# KIT_STM32F103C8T6.net
KiCad netlist of a schematic drawn in Altium Designer
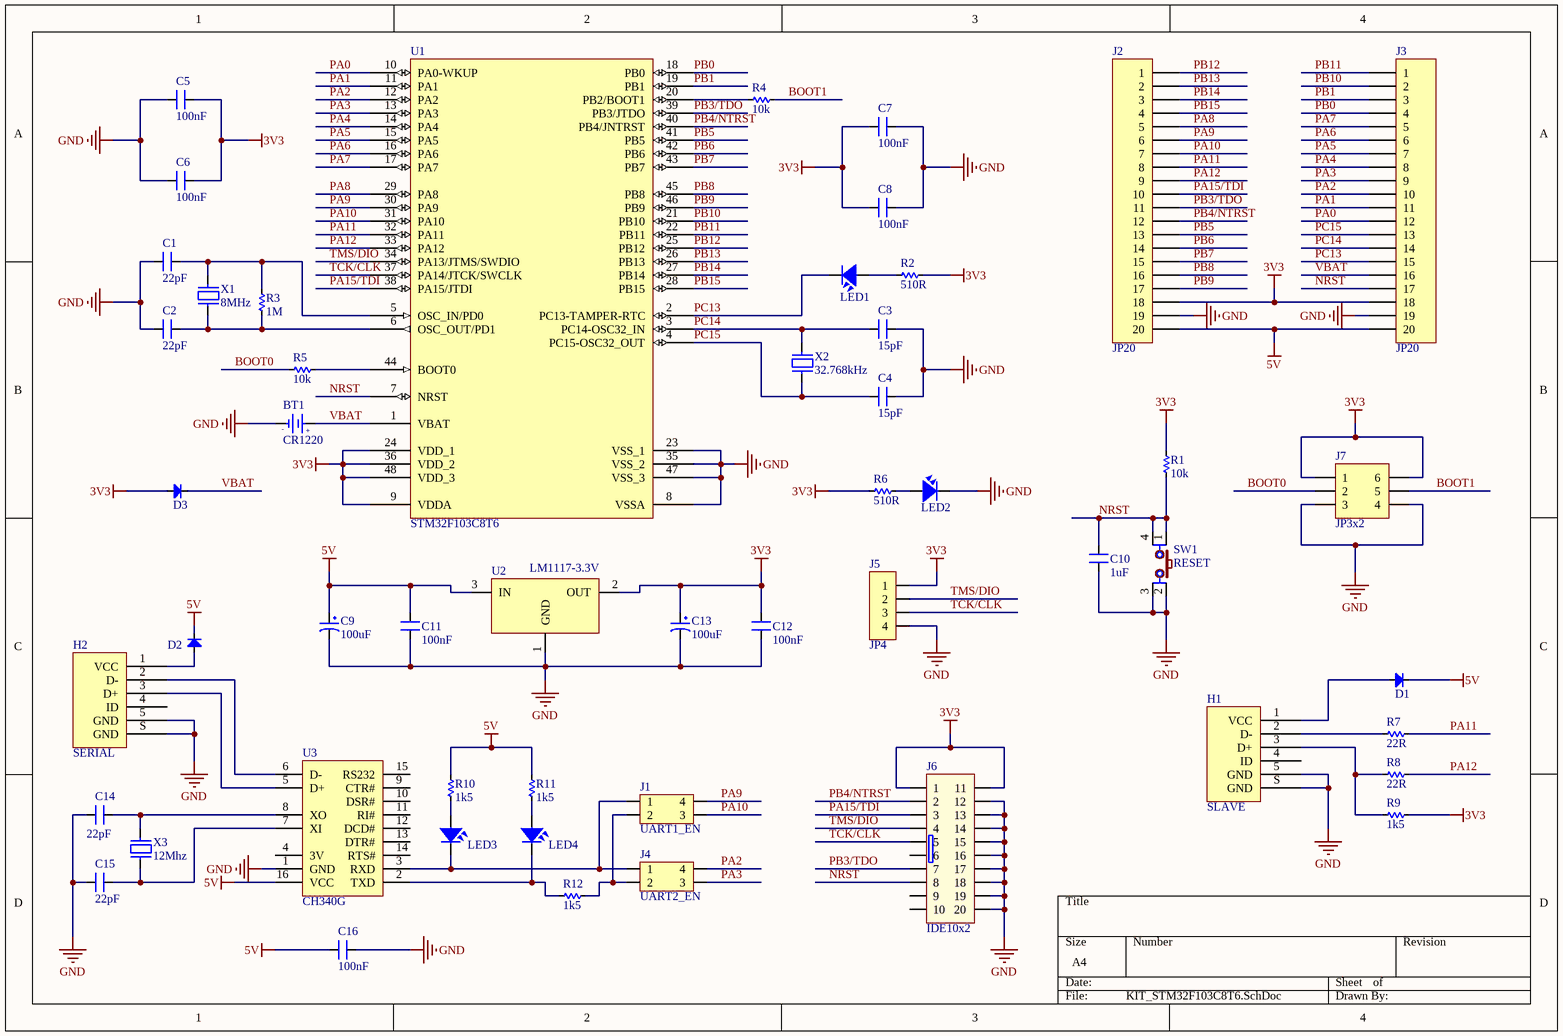
[diagram p0: KIT_STM32F103C8T6.SchDoc]

(export (version "E")
  (design (tool "Eeschema 10.0.6"))
  (components
    (comp (ref "BT1") (value "CR1220") (footprint "PIN CR1220") (libsource (lib "User") (part "PIN CR1220")))
    (comp (ref "C1") (value "22pF") (footprint "CN-SMD-0805") (libsource (lib "LIBRARY") (part "CN")))
    (comp (ref "C2") (value "22pF") (footprint "CN-SMD-0805") (libsource (lib "LIBRARY") (part "CN")))
    (comp (ref "C3") (value "15pF") (footprint "CN-SMD-0805") (libsource (lib "LIBRARY") (part "CN")))
    (comp (ref "C4") (value "15pF") (footprint "CN-SMD-0805") (libsource (lib "LIBRARY") (part "CN")))
    (comp (ref "C5") (value "100nF") (footprint "CN-SMD-0805") (libsource (lib "LIBRARY") (part "CN")))
    (comp (ref "C6") (value "100nF") (footprint "CN-SMD-0805") (libsource (lib "LIBRARY") (part "CN")))
    (comp (ref "C7") (value "100nF") (footprint "CN-SMD-0805") (libsource (lib "LIBRARY") (part "CN")))
    (comp (ref "C8") (value "100nF") (footprint "CN-SMD-0805") (libsource (lib "LIBRARY") (part "CN")))
    (comp (ref "C9") (value "100uF") (footprint "TU TANTALUM") (libsource (lib "User") (part "CAP TANTALUM")))
    (comp (ref "C10") (value "1uF") (footprint "CN-SMD-0805") (libsource (lib "LIBRARY") (part "CN")))
    (comp (ref "C11") (value "100nF") (footprint "CN-SMD-0805") (libsource (lib "LIBRARY") (part "CN")))
    (comp (ref "C12") (value "100nF") (footprint "CN-SMD-0805") (libsource (lib "LIBRARY") (part "CN")))
    (comp (ref "C13")
      (value "100uF")
      (footprint "TU TANTALUM")
      (libsource (lib "User") (part "CAP TANTALUM"))
    )
    (comp (ref "C14") (value "22pF") (footprint "CN-SMD-0805") (libsource (lib "LIBRARY") (part "CN")))
    (comp (ref "C15") (value "22pF") (footprint "CN-SMD-0805") (libsource (lib "LIBRARY") (part "CN")))
    (comp (ref "C16") (value "100nF") (footprint "CN-SMD-0805") (libsource (lib "LIBRARY") (part "CN")))
    (comp (ref "D1")
      (value "T4")
      (footprint "DIO-SMD-106")
      (description "Default Diode")
      (fields (field (name "PUBLISHER") "Altium Limited"))
      (libsource (lib "LIBRARY") (part "Diode SMD"))
    )
    (comp (ref "D2")
      (value "T4")
      (footprint "DIO-SMD-106")
      (description "Default Diode")
      (fields (field (name "PUBLISHER") "Altium Limited"))
      (libsource (lib "LIBRARY") (part "Diode SMD"))
    )
    (comp (ref "D3")
      (value "T4")
      (footprint "DIO-SMD-106")
      (description "Default Diode")
      (fields (field (name "PUBLISHER") "Altium Limited"))
      (libsource (lib "LIBRARY") (part "Diode SMD"))
    )
    (comp (ref "H1") (value "SLAVE") (footprint "MINI USB") (libsource (lib "User") (part "MINI USB")))
    (comp (ref "H2") (value "SERIAL") (footprint "MINI USB") (libsource (lib "User") (part "MINI USB")))
    (comp (ref "J1")
      (value "UART1_EN")
      (footprint "JP2-D2T")
      (description "WR-PHD 2.54 mm Dual Socket Header")
      (fields
        (field (name "MANUFACTURER") "Würth Elektronik eiSos GmbH")
        (field (name "PARTNO") "61300421821")
        (field (name "CREATED BY") "Karrer Zheng")
      )
      (libsource (lib "LIBRARY") (part "JP2x2"))
    )
    (comp (ref "J2")
      (value "JP20")
      (footprint "JP20-D1T")
      (description "WR-PHD 2.54 mm Angled Socket Header")
      (fields
        (field (name "MANUFACTURER") "Würth Elektronik eiSos GmbH")
        (field (name "PARTNO") "613020143121")
        (field (name "CREATED BY") "Karrer Zheng")
      )
      (libsource (lib "LIBRARY") (part "JP20"))
    )
    (comp (ref "J3")
      (value "JP20")
      (footprint "JP20-D1T")
      (description "WR-PHD 2.54 mm Angled Socket Header")
      (fields
        (field (name "MANUFACTURER") "Würth Elektronik eiSos GmbH")
        (field (name "PARTNO") "613020143121")
        (field (name "CREATED BY") "Karrer Zheng")
      )
      (libsource (lib "") (part "JP20_1"))
    )
    (comp (ref "J4")
      (value "UART2_EN")
      (footprint "JP2-D2T")
      (description "WR-PHD 2.54 mm Dual Socket Header")
      (fields
        (field (name "MANUFACTURER") "Würth Elektronik eiSos GmbH")
        (field (name "PARTNO") "61300421821")
        (field (name "CREATED BY") "Karrer Zheng")
      )
      (libsource (lib "LIBRARY") (part "JP2x2"))
    )
    (comp (ref "J5")
      (value "JP4")
      (footprint "JP4-D1T")
      (description "WR-PHD 2.54 mm Angled Socket Header")
      (fields
        (field (name "MANUFACTURER") "Würth Elektronik eiSos GmbH")
        (field (name "PARTNO") "613004143121")
        (field (name "CREATED BY") "Karrer Zheng")
      )
      (libsource (lib "LIBRARY") (part "JP4"))
    )
    (comp (ref "J6")
      (value "IDE10x2")
      (footprint "IDC20")
      (description "IDC 10x2")
      (libsource (lib "LIBRARY") (part "IDC 10X2"))
    )
    (comp (ref "J7")
      (value "JP3x2")
      (footprint "JP3-D2T")
      (description "WR-PHD 2.54 mm Dual Socket Header")
      (fields
        (field (name "MANUFACTURER") "Würth Elektronik eiSos GmbH")
        (field (name "PARTNO") "61300621821")
        (field (name "CREATED BY") "Karrer Zheng")
      )
      (libsource (lib "LIBRARY") (part "JP3x2"))
    )
    (comp (ref "LED1") (value "L") (footprint "LED-0805-Green") (libsource (lib "LIBRARY") (part "LED SMD")))
    (comp (ref "LED2")
      (value "PWR")
      (footprint "LED-0805-Green")
      (libsource (lib "LIBRARY") (part "LED SMD"))
    )
    (comp (ref "LED3") (value "R") (footprint "LED-0805-Green") (libsource (lib "LIBRARY") (part "LED SMD")))
    (comp (ref "LED4") (value "T") (footprint "LED-0805-Green") (libsource (lib "LIBRARY") (part "LED SMD")))
    (comp (ref "R1")
      (value "10k")
      (footprint "RES-SMD-0805")
      (description "Resistor")
      (fields
        (field (name "MANUFACTURER") "Generic Components")
        (field (name "PUBLISHER") "Altium Hobart Technology Centre")
      )
      (libsource (lib "LIBRARY") (part "Res-SMD"))
    )
    (comp (ref "R2")
      (value "510R")
      (footprint "RES-SMD-0805")
      (description "Resistor")
      (fields
        (field (name "MANUFACTURER") "Generic Components")
        (field (name "PUBLISHER") "Altium Hobart Technology Centre")
      )
      (libsource (lib "LIBRARY") (part "Res-SMD"))
    )
    (comp (ref "R3")
      (value "1M")
      (footprint "RES-SMD-0805")
      (description "Resistor")
      (fields
        (field (name "MANUFACTURER") "Generic Components")
        (field (name "PUBLISHER") "Altium Hobart Technology Centre")
      )
      (libsource (lib "LIBRARY") (part "Res-SMD"))
    )
    (comp (ref "R4")
      (value "10k")
      (footprint "RES-SMD-0805")
      (description "Resistor")
      (fields
        (field (name "MANUFACTURER") "Generic Components")
        (field (name "PUBLISHER") "Altium Hobart Technology Centre")
      )
      (libsource (lib "LIBRARY") (part "Res-SMD"))
    )
    (comp (ref "R5")
      (value "10k")
      (footprint "RES-SMD-0805")
      (description "Resistor")
      (fields
        (field (name "MANUFACTURER") "Generic Components")
        (field (name "PUBLISHER") "Altium Hobart Technology Centre")
      )
      (libsource (lib "LIBRARY") (part "Res-SMD"))
    )
    (comp (ref "R6")
      (value "510R")
      (footprint "RES-SMD-0805")
      (description "Resistor")
      (fields
        (field (name "MANUFACTURER") "Generic Components")
        (field (name "PUBLISHER") "Altium Hobart Technology Centre")
      )
      (libsource (lib "LIBRARY") (part "Res-SMD"))
    )
    (comp (ref "R7")
      (value "22R")
      (footprint "RES-SMD-0805")
      (description "Resistor")
      (fields
        (field (name "MANUFACTURER") "Generic Components")
        (field (name "PUBLISHER") "Altium Hobart Technology Centre")
      )
      (libsource (lib "LIBRARY") (part "Res-SMD"))
    )
    (comp (ref "R8")
      (value "22R")
      (footprint "RES-SMD-0805")
      (description "Resistor")
      (fields
        (field (name "MANUFACTURER") "Generic Components")
        (field (name "PUBLISHER") "Altium Hobart Technology Centre")
      )
      (libsource (lib "LIBRARY") (part "Res-SMD"))
    )
    (comp (ref "R9")
      (value "1k5")
      (footprint "RES-SMD-0805")
      (description "Resistor")
      (fields
        (field (name "MANUFACTURER") "Generic Components")
        (field (name "PUBLISHER") "Altium Hobart Technology Centre")
      )
      (libsource (lib "LIBRARY") (part "Res-SMD"))
    )
    (comp (ref "R10")
      (value "1k5")
      (footprint "RES-SMD-0805")
      (description "Resistor")
      (fields
        (field (name "MANUFACTURER") "Generic Components")
        (field (name "PUBLISHER") "Altium Hobart Technology Centre")
      )
      (libsource (lib "LIBRARY") (part "Res-SMD"))
    )
    (comp (ref "R11")
      (value "1k5")
      (footprint "RES-SMD-0805")
      (description "Resistor")
      (fields
        (field (name "MANUFACTURER") "Generic Components")
        (field (name "PUBLISHER") "Altium Hobart Technology Centre")
      )
      (libsource (lib "LIBRARY") (part "Res-SMD"))
    )
    (comp (ref "R12")
      (value "1k5")
      (footprint "RES-SMD-0805")
      (description "Resistor")
      (fields
        (field (name "MANUFACTURER") "Generic Components")
        (field (name "PUBLISHER") "Altium Hobart Technology Centre")
      )
      (libsource (lib "LIBRARY") (part "Res-SMD"))
    )
    (comp (ref "SW1")
      (value "RESET")
      (footprint "SW2-SMD")
      (description "Switch button 4 pin")
      (libsource (lib "LIBRARY") (part "SW4"))
    )
    (comp (ref "U1")
      (value "STM32F103C8T6")
      (footprint "LQFP48")
      (libsource (lib "User") (part "STM32F103C8T6"))
    )
    (comp (ref "U2")
      (value "LM1117-3.3V")
      (footprint "SOT223")
      (description "800mA Low-Dropout Linear Regulator")
      (fields (field (name "CREATOR") "Nguyen Ba Bien"))
      (libsource (lib "LIBRARY") (part "LM1117"))
    )
    (comp (ref "U3")
      (value "CH340G")
      (footprint "SO16")
      (description "High and Low Side Driver")
      (fields (field (name "PUBLISHER") "Altium Limited"))
      (libsource (lib "LIBRARY") (part "CH340G"))
    )
    (comp (ref "X1")
      (value "8MHz")
      (footprint "XT2")
      (description "Crystal, 32.768 KHz, -40 to 85 degC, 3.2 x 1.5 x 0.9 mm SMD")
      (libsource (lib "LIBRARY") (part "XT2"))
    )
    (comp (ref "X2")
      (value "32.768kHz")
      (footprint "XT32k")
      (description "Crystal, 32.768 KHz, -40 to 85 degC, 3.2 x 1.5 x 0.9 mm SMD")
      (libsource (lib "LIBRARY") (part "XT2"))
    )
    (comp (ref "X3")
      (value "12Mhz")
      (footprint "XT2")
      (description "Crystal, 32.768 KHz, -40 to 85 degC, 3.2 x 1.5 x 0.9 mm SMD")
      (libsource (lib "LIBRARY") (part "XT2"))
    )
  )
  (nets
    (net (code "1") (name "/BOOT0") (class "Default")
      (node (ref "J7") (pin "2") (pinfunction "2_2") (pintype "passive"))
      (node (ref "R5") (pin "2") (pinfunction "2_2") (pintype "passive"))
    )
    (net (code "2") (name "/BOOT1") (class "Default")
      (node (ref "J7") (pin "5") (pinfunction "5_5") (pintype "passive"))
      (node (ref "R4") (pin "1") (pinfunction "1_1") (pintype "passive"))
    )
    (net (code "3") (name "/NRST") (class "Default")
      (node (ref "C10") (pin "2") (pinfunction "2_2") (pintype "passive"))
      (node (ref "J3") (pin "17") (pinfunction "17_17") (pintype "passive"))
      (node (ref "J6") (pin "8") (pinfunction "8_8") (pintype "passive"))
      (node (ref "R1") (pin "2") (pinfunction "2_2") (pintype "passive"))
      (node (ref "SW1") (pin "1") (pintype "passive"))
      (node (ref "SW1") (pin "4") (pinfunction "4_4") (pintype "passive"))
      (node (ref "U1") (pin "7") (pinfunction "NRST_7") (pintype "bidirectional"))
    )
    (net (code "4") (name "/PA0") (class "Default")
      (node (ref "J3") (pin "12") (pinfunction "12_12") (pintype "passive"))
      (node (ref "U1") (pin "10") (pinfunction "PA0-WKUP_10") (pintype "bidirectional"))
    )
    (net (code "5") (name "/PA1") (class "Default")
      (node (ref "J3") (pin "11") (pinfunction "11_11") (pintype "passive"))
      (node (ref "U1") (pin "11") (pinfunction "PA1_11") (pintype "bidirectional"))
    )
    (net (code "6") (name "/PA2") (class "Default")
      (node (ref "J3") (pin "10") (pinfunction "10_10") (pintype "passive"))
      (node (ref "J4") (pin "4") (pinfunction "4_4") (pintype "passive"))
      (node (ref "U1") (pin "12") (pinfunction "PA2_12") (pintype "bidirectional"))
    )
    (net (code "7") (name "/PA3") (class "Default")
      (node (ref "J3") (pin "9") (pinfunction "9_9") (pintype "passive"))
      (node (ref "J4") (pin "3") (pinfunction "3_3") (pintype "passive"))
      (node (ref "U1") (pin "13") (pinfunction "PA3_13") (pintype "bidirectional"))
    )
    (net (code "8") (name "/PA4") (class "Default")
      (node (ref "J3") (pin "8") (pinfunction "8_8") (pintype "passive"))
      (node (ref "U1") (pin "14") (pinfunction "PA4_14") (pintype "bidirectional"))
    )
    (net (code "9") (name "/PA5") (class "Default")
      (node (ref "J3") (pin "7") (pinfunction "7_7") (pintype "passive"))
      (node (ref "U1") (pin "15") (pinfunction "PA5_15") (pintype "bidirectional"))
    )
    (net (code "10") (name "/PA6") (class "Default")
      (node (ref "J3") (pin "6") (pinfunction "6_6") (pintype "passive"))
      (node (ref "U1") (pin "16") (pinfunction "PA6_16") (pintype "bidirectional"))
    )
    (net (code "11") (name "/PA7") (class "Default")
      (node (ref "J3") (pin "5") (pinfunction "5_5") (pintype "passive"))
      (node (ref "U1") (pin "17") (pinfunction "PA7_17") (pintype "bidirectional"))
    )
    (net (code "12") (name "/PA8") (class "Default")
      (node (ref "J2") (pin "5") (pinfunction "5_5") (pintype "passive"))
      (node (ref "U1") (pin "29") (pinfunction "PA8_29") (pintype "bidirectional"))
    )
    (net (code "13") (name "/PA9") (class "Default")
      (node (ref "J1") (pin "4") (pinfunction "4_4") (pintype "passive"))
      (node (ref "J2") (pin "6") (pinfunction "6_6") (pintype "passive"))
      (node (ref "U1") (pin "30") (pinfunction "PA9_30") (pintype "bidirectional"))
    )
    (net (code "14") (name "/PA10") (class "Default")
      (node (ref "J1") (pin "3") (pinfunction "3_3") (pintype "passive"))
      (node (ref "J2") (pin "7") (pinfunction "7_7") (pintype "passive"))
      (node (ref "U1") (pin "31") (pinfunction "PA10_31") (pintype "bidirectional"))
    )
    (net (code "15") (name "/PA11") (class "Default")
      (node (ref "J2") (pin "8") (pinfunction "8_8") (pintype "passive"))
      (node (ref "R7") (pin "1") (pinfunction "1_1") (pintype "passive"))
      (node (ref "U1") (pin "32") (pinfunction "PA11_32") (pintype "bidirectional"))
    )
    (net (code "16") (name "/PA12") (class "Default")
      (node (ref "J2") (pin "9") (pinfunction "9_9") (pintype "passive"))
      (node (ref "R8") (pin "1") (pinfunction "1_1") (pintype "passive"))
      (node (ref "U1") (pin "33") (pinfunction "PA12_33") (pintype "bidirectional"))
    )
    (net (code "17") (name "/PA15{slash}TDI") (class "Default")
      (node (ref "J2") (pin "10") (pinfunction "10_10") (pintype "passive"))
      (node (ref "J6") (pin "3") (pinfunction "3_3") (pintype "passive"))
      (node (ref "U1") (pin "38") (pinfunction "PA15/JTDI_38") (pintype "bidirectional"))
    )
    (net (code "18") (name "/PB0") (class "Default")
      (node (ref "J3") (pin "4") (pinfunction "4_4") (pintype "passive"))
      (node (ref "U1") (pin "18") (pinfunction "PB0_18") (pintype "bidirectional"))
    )
    (net (code "19") (name "/PB1") (class "Default")
      (node (ref "J3") (pin "3") (pinfunction "3_3") (pintype "passive"))
      (node (ref "U1") (pin "19") (pinfunction "PB1_19") (pintype "bidirectional"))
    )
    (net (code "20") (name "/PB3{slash}TDO") (class "Default")
      (node (ref "J2") (pin "11") (pinfunction "11_11") (pintype "passive"))
      (node (ref "J6") (pin "7") (pinfunction "7_7") (pintype "passive"))
      (node (ref "U1") (pin "39") (pinfunction "PB3/JTDO_39") (pintype "bidirectional"))
    )
    (net (code "21") (name "/PB4{slash}NTRST") (class "Default")
      (node (ref "J2") (pin "12") (pinfunction "12_12") (pintype "passive"))
      (node (ref "J6") (pin "2") (pinfunction "2_2") (pintype "passive"))
      (node (ref "U1") (pin "40") (pinfunction "PB4/JNTRST_40") (pintype "bidirectional"))
    )
    (net (code "22") (name "/PB5") (class "Default")
      (node (ref "J2") (pin "13") (pinfunction "13_13") (pintype "passive"))
      (node (ref "U1") (pin "41") (pinfunction "PB5_41") (pintype "bidirectional"))
    )
    (net (code "23") (name "/PB6") (class "Default")
      (node (ref "J2") (pin "14") (pinfunction "14_14") (pintype "passive"))
      (node (ref "U1") (pin "42") (pinfunction "PB6_42") (pintype "bidirectional"))
    )
    (net (code "24") (name "/PB7") (class "Default")
      (node (ref "J2") (pin "15") (pinfunction "15_15") (pintype "passive"))
      (node (ref "U1") (pin "43") (pinfunction "PB7_43") (pintype "bidirectional"))
    )
    (net (code "25") (name "/PB8") (class "Default")
      (node (ref "J2") (pin "16") (pinfunction "16_16") (pintype "passive"))
      (node (ref "U1") (pin "45") (pinfunction "PB8_45") (pintype "bidirectional"))
    )
    (net (code "26") (name "/PB9") (class "Default")
      (node (ref "J2") (pin "17") (pinfunction "17_17") (pintype "passive"))
      (node (ref "U1") (pin "46") (pinfunction "PB9_46") (pintype "bidirectional"))
    )
    (net (code "27") (name "/PB10") (class "Default")
      (node (ref "J3") (pin "2") (pinfunction "2_2") (pintype "passive"))
      (node (ref "U1") (pin "21") (pinfunction "PB10_21") (pintype "bidirectional"))
    )
    (net (code "28") (name "/PB11") (class "Default")
      (node (ref "J3") (pin "1") (pinfunction "1_1") (pintype "passive"))
      (node (ref "U1") (pin "22") (pinfunction "PB11_22") (pintype "bidirectional"))
    )
    (net (code "29") (name "/PB12") (class "Default")
      (node (ref "J2") (pin "1") (pinfunction "1_1") (pintype "passive"))
      (node (ref "U1") (pin "25") (pinfunction "PB12_25") (pintype "bidirectional"))
    )
    (net (code "30") (name "/PB13") (class "Default")
      (node (ref "J2") (pin "2") (pinfunction "2_2") (pintype "passive"))
      (node (ref "U1") (pin "26") (pinfunction "PB13_26") (pintype "bidirectional"))
    )
    (net (code "31") (name "/PB14") (class "Default")
      (node (ref "J2") (pin "3") (pinfunction "3_3") (pintype "passive"))
      (node (ref "U1") (pin "27") (pinfunction "PB14_27") (pintype "bidirectional"))
    )
    (net (code "32") (name "/PB15") (class "Default")
      (node (ref "J2") (pin "4") (pinfunction "4_4") (pintype "passive"))
      (node (ref "U1") (pin "28") (pinfunction "PB15_28") (pintype "bidirectional"))
    )
    (net (code "33") (name "/PC13") (class "Default")
      (node (ref "J3") (pin "15") (pinfunction "15_15") (pintype "passive"))
      (node (ref "LED1") (pin "2") (pinfunction "2_2") (pintype "passive"))
      (node (ref "U1") (pin "2") (pinfunction "PC13-TAMPER-RTC_2") (pintype "bidirectional"))
    )
    (net (code "34") (name "/PC14") (class "Default")
      (node (ref "C3") (pin "1") (pinfunction "1_1") (pintype "passive"))
      (node (ref "J3") (pin "14") (pinfunction "14_14") (pintype "passive"))
      (node (ref "U1") (pin "3") (pinfunction "PC14-OSC32_IN_3") (pintype "bidirectional"))
      (node (ref "X2") (pin "2") (pinfunction "2_2") (pintype "passive"))
    )
    (net (code "35") (name "/PC15") (class "Default")
      (node (ref "C4") (pin "1") (pinfunction "1_1") (pintype "passive"))
      (node (ref "J3") (pin "13") (pinfunction "13_13") (pintype "passive"))
      (node (ref "U1") (pin "4") (pinfunction "PC15-OSC32_OUT_4") (pintype "bidirectional"))
      (node (ref "X2") (pin "1") (pinfunction "1_1") (pintype "passive"))
    )
    (net (code "36") (name "/TCK{slash}CLK") (class "Default")
      (node (ref "J5") (pin "3") (pinfunction "3_3") (pintype "passive"))
      (node (ref "J6") (pin "5") (pinfunction "5_5") (pintype "passive"))
      (node (ref "U1") (pin "37") (pinfunction "PA14/JTCK/SWCLK_37") (pintype "bidirectional"))
    )
    (net (code "37") (name "/TMS{slash}DIO") (class "Default")
      (node (ref "J5") (pin "2") (pinfunction "2_2") (pintype "passive"))
      (node (ref "J6") (pin "4") (pinfunction "4_4") (pintype "passive"))
      (node (ref "U1") (pin "34") (pinfunction "PA13/JTMS/SWDIO_34") (pintype "bidirectional"))
    )
    (net (code "38") (name "/VBAT") (class "Default")
      (node (ref "BT1") (pin "1") (pinfunction "+3V_1") (pintype "passive"))
      (node (ref "D3") (pin "2") (pinfunction "K_2") (pintype "passive"))
      (node (ref "J3") (pin "16") (pinfunction "16_16") (pintype "passive"))
      (node (ref "U1") (pin "1") (pinfunction "VBAT_1") (pintype "power_in"))
    )
    (net (code "39") (name "3V3") (class "Default")
      (node (ref "C12") (pin "1") (pinfunction "1_1") (pintype "passive"))
      (node (ref "C13") (pin "1") (pinfunction "1_1") (pintype "passive"))
      (node (ref "C5") (pin "2") (pinfunction "2_2") (pintype "passive"))
      (node (ref "C6") (pin "2") (pinfunction "2_2") (pintype "passive"))
      (node (ref "C7") (pin "2") (pinfunction "2_2") (pintype "passive"))
      (node (ref "C8") (pin "2") (pinfunction "2_2") (pintype "passive"))
      (node (ref "D3") (pin "1") (pinfunction "A_1") (pintype "passive"))
      (node (ref "J2") (pin "18") (pinfunction "18_18") (pintype "passive"))
      (node (ref "J3") (pin "18") (pinfunction "18_18") (pintype "passive"))
      (node (ref "J5") (pin "1") (pinfunction "1_1") (pintype "passive"))
      (node (ref "J6") (pin "1") (pinfunction "1_1") (pintype "passive"))
      (node (ref "J6") (pin "11") (pinfunction "11_11") (pintype "passive"))
      (node (ref "J7") (pin "1") (pinfunction "1_1") (pintype "passive"))
      (node (ref "J7") (pin "6") (pinfunction "6_6") (pintype "passive"))
      (node (ref "R1") (pin "1") (pinfunction "1_1") (pintype "passive"))
      (node (ref "R2") (pin "1") (pinfunction "1_1") (pintype "passive"))
      (node (ref "R6") (pin "2") (pinfunction "2_2") (pintype "passive"))
      (node (ref "R9") (pin "1") (pinfunction "1_1") (pintype "passive"))
      (node (ref "U1") (pin "24") (pinfunction "VDD_1_24") (pintype "power_in"))
      (node (ref "U1") (pin "36") (pinfunction "VDD_2_36") (pintype "power_in"))
      (node (ref "U1") (pin "48") (pinfunction "VDD_3_48") (pintype "power_in"))
      (node (ref "U1") (pin "9") (pinfunction "VDDA_9") (pintype "power_in"))
      (node (ref "U2") (pin "2") (pinfunction "OUT_2") (pintype "passive"))
    )
    (net (code "40") (name "5V") (class "Default")
      (node (ref "C11") (pin "1") (pinfunction "1_1") (pintype "passive"))
      (node (ref "C16") (pin "2") (pinfunction "2_2") (pintype "passive"))
      (node (ref "C9") (pin "1") (pinfunction "1_1") (pintype "passive"))
      (node (ref "D1") (pin "2") (pinfunction "K_2") (pintype "passive"))
      (node (ref "D2") (pin "2") (pinfunction "K_2") (pintype "passive"))
      (node (ref "J2") (pin "20") (pinfunction "20_20") (pintype "passive"))
      (node (ref "J3") (pin "20") (pinfunction "20_20") (pintype "passive"))
      (node (ref "R10") (pin "1") (pinfunction "1_1") (pintype "passive"))
      (node (ref "R11") (pin "1") (pinfunction "1_1") (pintype "passive"))
      (node (ref "U2") (pin "3") (pinfunction "IN_3") (pintype "passive"))
      (node (ref "U3") (pin "16") (pinfunction "VCC_16") (pintype "passive"))
    )
    (net (code "41") (name "GND") (class "Default")
      (node (ref "BT1") (pin "2") (pinfunction "GND_2") (pintype "passive"))
      (node (ref "C1") (pin "1") (pinfunction "1_1") (pintype "passive"))
      (node (ref "C10") (pin "1") (pinfunction "1_1") (pintype "passive"))
      (node (ref "C11") (pin "2") (pinfunction "2_2") (pintype "passive"))
      (node (ref "C12") (pin "2") (pinfunction "2_2") (pintype "passive"))
      (node (ref "C13") (pin "2") (pinfunction "2_2") (pintype "passive"))
      (node (ref "C14") (pin "2") (pinfunction "2_2") (pintype "passive"))
      (node (ref "C15") (pin "2") (pinfunction "2_2") (pintype "passive"))
      (node (ref "C16") (pin "1") (pinfunction "1_1") (pintype "passive"))
      (node (ref "C2") (pin "1") (pinfunction "1_1") (pintype "passive"))
      (node (ref "C3") (pin "2") (pinfunction "2_2") (pintype "passive"))
      (node (ref "C4") (pin "2") (pinfunction "2_2") (pintype "passive"))
      (node (ref "C5") (pin "1") (pinfunction "1_1") (pintype "passive"))
      (node (ref "C6") (pin "1") (pinfunction "1_1") (pintype "passive"))
      (node (ref "C7") (pin "1") (pinfunction "1_1") (pintype "passive"))
      (node (ref "C8") (pin "1") (pinfunction "1_1") (pintype "passive"))
      (node (ref "C9") (pin "2") (pinfunction "2_2") (pintype "passive"))
      (node (ref "H1") (pin "5") (pinfunction "GND_5") (pintype "passive"))
      (node (ref "H1") (pin "S") (pinfunction "GND_S") (pintype "passive"))
      (node (ref "H2") (pin "5") (pinfunction "GND_5") (pintype "passive"))
      (node (ref "H2") (pin "S") (pinfunction "GND_S") (pintype "passive"))
      (node (ref "J2") (pin "19") (pinfunction "19_19") (pintype "passive"))
      (node (ref "J3") (pin "19") (pinfunction "19_19") (pintype "passive"))
      (node (ref "J5") (pin "4") (pinfunction "4_4") (pintype "passive"))
      (node (ref "J6") (pin "12") (pinfunction "12_12") (pintype "passive"))
      (node (ref "J6") (pin "13") (pinfunction "13_13") (pintype "passive"))
      (node (ref "J6") (pin "14") (pinfunction "14_14") (pintype "passive"))
      (node (ref "J6") (pin "15") (pinfunction "15_15") (pintype "passive"))
      (node (ref "J6") (pin "16") (pinfunction "16_16") (pintype "passive"))
      (node (ref "J6") (pin "17") (pinfunction "17_17") (pintype "passive"))
      (node (ref "J6") (pin "18") (pinfunction "18_18") (pintype "passive"))
      (node (ref "J6") (pin "19") (pinfunction "19_19") (pintype "passive"))
      (node (ref "J6") (pin "20") (pinfunction "20_20") (pintype "passive"))
      (node (ref "J7") (pin "3") (pinfunction "3_3") (pintype "passive"))
      (node (ref "J7") (pin "4") (pinfunction "4_4") (pintype "passive"))
      (node (ref "LED2") (pin "2") (pinfunction "2_2") (pintype "passive"))
      (node (ref "SW1") (pin "2") (pinfunction "2_2") (pintype "passive"))
      (node (ref "SW1") (pin "3") (pinfunction "3_3") (pintype "passive"))
      (node (ref "U1") (pin "23") (pinfunction "VSS_1_23") (pintype "power_in"))
      (node (ref "U1") (pin "35") (pinfunction "VSS_2_35") (pintype "power_in"))
      (node (ref "U1") (pin "47") (pinfunction "VSS_3_47") (pintype "power_in"))
      (node (ref "U1") (pin "8") (pinfunction "VSSA_8") (pintype "power_in"))
      (node (ref "U2") (pin "1") (pinfunction "GND_1") (pintype "passive"))
      (node (ref "U3") (pin "1") (pinfunction "GND_1") (pintype "passive"))
    )
    (net (code "42") (name "Net-(D1-A)") (class "Default")
      (node (ref "D1") (pin "1") (pinfunction "A_1") (pintype "passive"))
      (node (ref "H1") (pin "1") (pinfunction "VCC_1") (pintype "passive"))
    )
    (net (code "43") (name "Net-(D2-A)") (class "Default")
      (node (ref "D2") (pin "1") (pinfunction "A_1") (pintype "passive"))
      (node (ref "H2") (pin "1") (pinfunction "VCC_1") (pintype "passive"))
    )
    (net (code "44") (name "Net-(H1-D+)") (class "Default")
      (node (ref "H1") (pin "3") (pinfunction "D+_3") (pintype "passive"))
      (node (ref "R8") (pin "2") (pinfunction "2_2") (pintype "passive"))
      (node (ref "R9") (pin "2") (pinfunction "2_2") (pintype "passive"))
    )
    (net (code "45") (name "Net-(H1-D-)") (class "Default")
      (node (ref "H1") (pin "2") (pinfunction "D-_2") (pintype "passive"))
      (node (ref "R7") (pin "2") (pinfunction "2_2") (pintype "passive"))
    )
    (net (code "46") (name "Net-(H2-D+)") (class "Default")
      (node (ref "H2") (pin "3") (pinfunction "D+_3") (pintype "passive"))
      (node (ref "U3") (pin "5") (pinfunction "D+_5") (pintype "passive"))
    )
    (net (code "47") (name "Net-(H2-D-)") (class "Default")
      (node (ref "H2") (pin "2") (pinfunction "D-_2") (pintype "passive"))
      (node (ref "U3") (pin "6") (pinfunction "D-_6") (pintype "passive"))
    )
    (net (code "48") (name "Net-(J1-Pad2)") (class "Default")
      (node (ref "J1") (pin "2") (pinfunction "2_2") (pintype "passive"))
      (node (ref "J4") (pin "2") (pinfunction "2_2") (pintype "passive"))
      (node (ref "R12") (pin "1") (pinfunction "1_1") (pintype "passive"))
    )
    (net (code "49") (name "Net-(LED1-Pad1)") (class "Default")
      (node (ref "LED1") (pin "1") (pinfunction "1_1") (pintype "passive"))
      (node (ref "R2") (pin "2") (pinfunction "2_2") (pintype "passive"))
    )
    (net (code "50") (name "Net-(LED2-Pad1)") (class "Default")
      (node (ref "LED2") (pin "1") (pinfunction "1_1") (pintype "passive"))
      (node (ref "R6") (pin "1") (pinfunction "1_1") (pintype "passive"))
    )
    (net (code "51") (name "Net-(LED3-Pad1)") (class "Default")
      (node (ref "LED3") (pin "1") (pinfunction "1_1") (pintype "passive"))
      (node (ref "R10") (pin "2") (pinfunction "2_2") (pintype "passive"))
    )
    (net (code "52") (name "Net-(LED4-Pad1)") (class "Default")
      (node (ref "LED4") (pin "1") (pinfunction "1_1") (pintype "passive"))
      (node (ref "R11") (pin "2") (pinfunction "2_2") (pintype "passive"))
    )
    (net (code "53") (name "Net-(U1-BOOT0)") (class "Default")
      (node (ref "R5") (pin "1") (pinfunction "1_1") (pintype "passive"))
      (node (ref "U1") (pin "44") (pinfunction "BOOT0_44") (pintype "input"))
    )
    (net (code "54") (name "Net-(U1-OSC_IN{slash}PD0)") (class "Default")
      (node (ref "C1") (pin "2") (pinfunction "2_2") (pintype "passive"))
      (node (ref "R3") (pin "1") (pinfunction "1_1") (pintype "passive"))
      (node (ref "U1") (pin "5") (pinfunction "OSC_IN/PD0_5") (pintype "input"))
      (node (ref "X1") (pin "2") (pinfunction "2_2") (pintype "passive"))
    )
    (net (code "55") (name "Net-(U1-OSC_OUT{slash}PD1)") (class "Default")
      (node (ref "C2") (pin "2") (pinfunction "2_2") (pintype "passive"))
      (node (ref "R3") (pin "2") (pinfunction "2_2") (pintype "passive"))
      (node (ref "U1") (pin "6") (pinfunction "OSC_OUT/PD1_6") (pintype "output"))
      (node (ref "X1") (pin "1") (pinfunction "1_1") (pintype "passive"))
    )
    (net (code "56") (name "Net-(U1-PB2{slash}BOOT1)") (class "Default")
      (node (ref "R4") (pin "2") (pinfunction "2_2") (pintype "passive"))
      (node (ref "U1") (pin "20") (pinfunction "PB2/BOOT1_20") (pintype "bidirectional"))
    )
    (net (code "57") (name "Net-(U3-RXD)") (class "Default")
      (node (ref "J1") (pin "1") (pinfunction "1_1") (pintype "passive"))
      (node (ref "J4") (pin "1") (pinfunction "1_1") (pintype "passive"))
      (node (ref "LED3") (pin "2") (pinfunction "2_2") (pintype "passive"))
      (node (ref "U3") (pin "3") (pinfunction "RXD_3") (pintype "passive"))
    )
    (net (code "58") (name "Net-(U3-TXD)") (class "Default")
      (node (ref "LED4") (pin "2") (pinfunction "2_2") (pintype "passive"))
      (node (ref "R12") (pin "2") (pinfunction "2_2") (pintype "passive"))
      (node (ref "U3") (pin "2") (pinfunction "TXD_2") (pintype "passive"))
    )
    (net (code "59") (name "Net-(U3-XI)") (class "Default")
      (node (ref "C15") (pin "1") (pinfunction "1_1") (pintype "passive"))
      (node (ref "U3") (pin "7") (pinfunction "XI_7") (pintype "passive"))
      (node (ref "X3") (pin "1") (pinfunction "1_1") (pintype "passive"))
    )
    (net (code "60") (name "Net-(U3-XO)") (class "Default")
      (node (ref "C14") (pin "1") (pinfunction "1_1") (pintype "passive"))
      (node (ref "U3") (pin "8") (pinfunction "XO_8") (pintype "passive"))
      (node (ref "X3") (pin "2") (pinfunction "2_2") (pintype "passive"))
    )
    (net (code "61") (name "unconnected-(H1-ID-Pad4)") (class "Default")
      (node (ref "H1") (pin "4") (pinfunction "ID_4") (pintype "passive"))
    )
    (net (code "62") (name "unconnected-(H2-ID-Pad4)") (class "Default")
      (node (ref "H2") (pin "4") (pinfunction "ID_4") (pintype "passive"))
    )
    (net (code "63") (name "unconnected-(J6-Pad6)") (class "Default")
      (node (ref "J6") (pin "6") (pinfunction "6_6") (pintype "passive"))
    )
    (net (code "64") (name "unconnected-(J6-Pad9)") (class "Default")
      (node (ref "J6") (pin "9") (pinfunction "9_9") (pintype "passive"))
    )
    (net (code "65") (name "unconnected-(J6-Pad10)") (class "Default")
      (node (ref "J6") (pin "10") (pinfunction "10_10") (pintype "passive"))
    )
    (net (code "66") (name "unconnected-(U3-3V-Pad4)") (class "Default")
      (node (ref "U3") (pin "4") (pinfunction "3V_4") (pintype "passive"))
    )
    (net (code "67") (name "unconnected-(U3-CTR#-Pad9)") (class "Default")
      (node (ref "U3") (pin "9") (pinfunction "CTR#_9") (pintype "passive"))
    )
    (net (code "68") (name "unconnected-(U3-DCD#-Pad12)") (class "Default")
      (node (ref "U3") (pin "12") (pinfunction "DCD#_12") (pintype "passive"))
    )
    (net (code "69") (name "unconnected-(U3-DSR#-Pad10)") (class "Default")
      (node (ref "U3") (pin "10") (pinfunction "DSR#_10") (pintype "passive"))
    )
    (net (code "70") (name "unconnected-(U3-DTR#-Pad13)") (class "Default")
      (node (ref "U3") (pin "13") (pinfunction "DTR#_13") (pintype "passive"))
    )
    (net (code "71") (name "unconnected-(U3-RI#-Pad11)") (class "Default")
      (node (ref "U3") (pin "11") (pinfunction "RI#_11") (pintype "passive"))
    )
    (net (code "72") (name "unconnected-(U3-RS232-Pad15)") (class "Default")
      (node (ref "U3") (pin "15") (pinfunction "RS232_15") (pintype "passive"))
    )
    (net (code "73") (name "unconnected-(U3-RTS#-Pad14)") (class "Default")
      (node (ref "U3") (pin "14") (pinfunction "RTS#_14") (pintype "passive"))
    )
  )
)
